# Adj.net
KiCad netlist of a schematic drawn in EAGLE
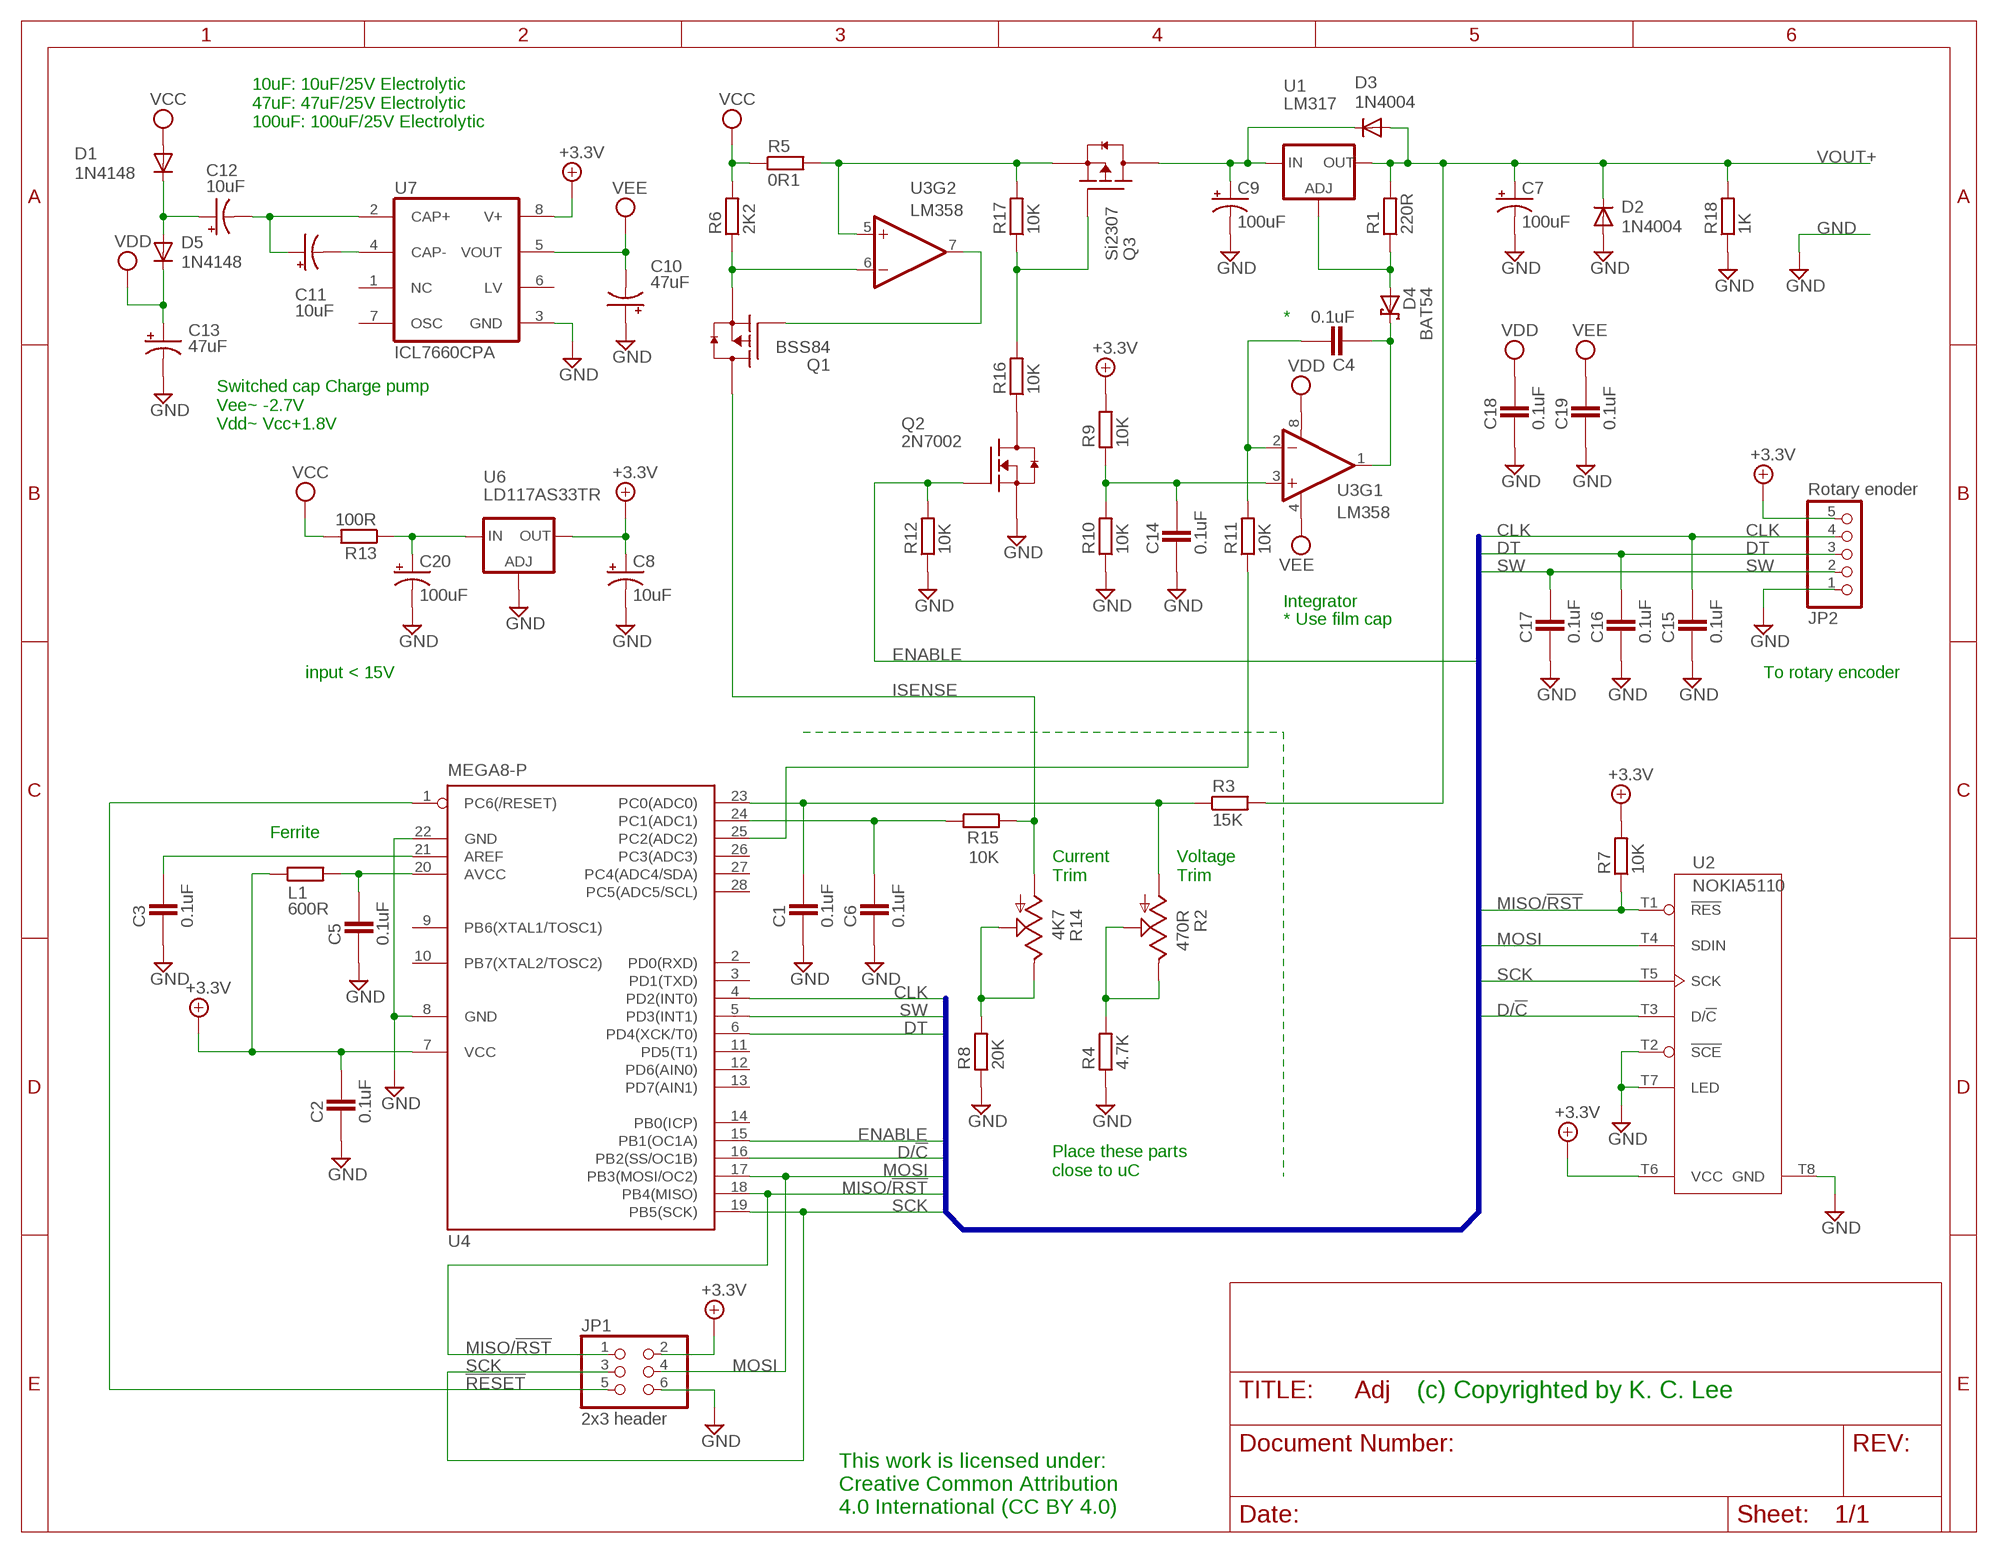
[diagram p0: schematic, sheet 1]

(export (version "E")
  (design (tool "Eeschema 10.0.6"))
  (components
    (comp (ref "C1")
      (value "0.1uF")
      (footprint "eagle-import:CAPC2012X145AN")
      (libsource (lib "eagle-import") (part "CAPACITOR_0805"))
    )
    (comp (ref "C2")
      (value "0.1uF")
      (footprint "eagle-import:CAPC2012X145AN")
      (libsource (lib "eagle-import") (part "CAPACITOR_0805"))
    )
    (comp (ref "C3")
      (value "0.1uF")
      (footprint "eagle-import:CAPC2012X145AN")
      (libsource (lib "eagle-import") (part "CAPACITOR_0805"))
    )
    (comp (ref "C4")
      (value "0.1uF")
      (footprint "eagle-import:CAPC2012X145AN")
      (libsource (lib "eagle-import") (part "CAPACITOR_0805"))
    )
    (comp (ref "C5")
      (value "0.1uF")
      (footprint "eagle-import:CAPC2012X145AN")
      (libsource (lib "eagle-import") (part "CAPACITOR_0805"))
    )
    (comp (ref "C6")
      (value "0.1uF")
      (footprint "eagle-import:CAPC2012X145AN")
      (libsource (lib "eagle-import") (part "CAPACITOR_0805"))
    )
    (comp (ref "C7")
      (value "100uF")
      (footprint "eagle-import:E2,5-6E")
      (fields (field (name "PARTNO") "100uF/25V"))
      (libsource (lib "eagle-import") (part "CAP_POL"))
    )
    (comp (ref "C8")
      (value "10uF")
      (footprint "eagle-import:E2,5-6E")
      (fields (field (name "PARTNO") "10uF/25V"))
      (libsource (lib "eagle-import") (part "CAP_POL"))
    )
    (comp (ref "C9")
      (value "100uF")
      (footprint "eagle-import:E2,5-6E")
      (fields (field (name "PARTNO") "100uF/25V"))
      (libsource (lib "eagle-import") (part "CAP_POL"))
    )
    (comp (ref "C10")
      (value "47uF")
      (footprint "eagle-import:E2,5-6E")
      (fields (field (name "PARTNO") "47uF/25V"))
      (libsource (lib "eagle-import") (part "CAP_POL"))
    )
    (comp (ref "C11")
      (value "10uF")
      (footprint "eagle-import:E2,5-6E")
      (fields (field (name "PARTNO") "10uF/25V"))
      (libsource (lib "eagle-import") (part "CAP_POL"))
    )
    (comp (ref "C12")
      (value "10uF")
      (footprint "eagle-import:E2,5-6E")
      (fields (field (name "PARTNO") "10uF/25V"))
      (libsource (lib "eagle-import") (part "CAP_POL"))
    )
    (comp (ref "C13")
      (value "47uF")
      (footprint "eagle-import:E2,5-6E")
      (fields (field (name "PARTNO") "47uF/25V"))
      (libsource (lib "eagle-import") (part "CAP_POL"))
    )
    (comp (ref "C14")
      (value "0.1uF")
      (footprint "eagle-import:CAPC2012X145AN")
      (libsource (lib "eagle-import") (part "CAPACITOR_0805"))
    )
    (comp (ref "C15")
      (value "0.1uF")
      (footprint "eagle-import:CAPC2012X145AN")
      (libsource (lib "eagle-import") (part "CAPACITOR_0805"))
    )
    (comp (ref "C16")
      (value "0.1uF")
      (footprint "eagle-import:CAPC2012X145AN")
      (libsource (lib "eagle-import") (part "CAPACITOR_0805"))
    )
    (comp (ref "C17")
      (value "0.1uF")
      (footprint "eagle-import:CAPC2012X145AN")
      (libsource (lib "eagle-import") (part "CAPACITOR_0805"))
    )
    (comp (ref "C18")
      (value "0.1uF")
      (footprint "eagle-import:CAPC2012X145AN")
      (libsource (lib "eagle-import") (part "CAPACITOR_0805"))
    )
    (comp (ref "C19")
      (value "0.1uF")
      (footprint "eagle-import:CAPC2012X145AN")
      (libsource (lib "eagle-import") (part "CAPACITOR_0805"))
    )
    (comp (ref "C20")
      (value "100uF")
      (footprint "eagle-import:E2,5-6E")
      (fields (field (name "PARTNO") "100uF/25V"))
      (libsource (lib "eagle-import") (part "CAP_POL"))
    )
    (comp (ref "D1")
      (value "1N4148")
      (footprint "eagle-import:DO35-7")
      (libsource (lib "eagle-import") (part "1N4148DO35-7"))
    )
    (comp (ref "D2")
      (value "1N4004")
      (footprint "eagle-import:DO41-10")
      (libsource (lib "eagle-import") (part "1N4004"))
    )
    (comp (ref "D3")
      (value "1N4004")
      (footprint "eagle-import:DO41-10")
      (libsource (lib "eagle-import") (part "1N4004"))
    )
    (comp (ref "D4")
      (value "BAT54")
      (footprint "eagle-import:SOT95P280X135-3N")
      (libsource (lib "eagle-import") (part "SCHOTTKY_SOT-23"))
    )
    (comp (ref "D5")
      (value "1N4148")
      (footprint "eagle-import:DO35-7")
      (libsource (lib "eagle-import") (part "1N4148DO35-7"))
    )
    (comp (ref "JP1")
      (value "2x3 header")
      (footprint "eagle-import:2X03")
      (libsource (lib "eagle-import") (part "PINHD-2X3_2.54"))
    )
    (comp (ref "JP2")
      (value "Rotary enoder")
      (footprint "eagle-import:1X05")
      (libsource (lib "eagle-import") (part "PINHD-1X5_2.54"))
    )
    (comp (ref "L1")
      (value "600R")
      (footprint "eagle-import:RESC1608X55N")
      (fields (field (name "PARTNO") "Ferrite 600R@100MHz"))
      (libsource (lib "eagle-import") (part "RESISTOR_0603"))
    )
    (comp (ref "Q1")
      (value "BSS84")
      (footprint "eagle-import:SOT95P280X135-3N")
      (libsource (lib "eagle-import") (part "MOSFET-PCH_SOT-23"))
    )
    (comp (ref "Q2")
      (value "2N7002")
      (footprint "eagle-import:SOT95P280X135-3N")
      (libsource (lib "eagle-import") (part "MOSFET-NCH_SOT-23"))
    )
    (comp (ref "Q3")
      (value "Si2307")
      (footprint "eagle-import:SOT95P280X135-3N")
      (libsource (lib "eagle-import") (part "MOSFET-PCH_SOT-23"))
    )
    (comp (ref "R1")
      (value "220R")
      (footprint "eagle-import:RESC1608X55N")
      (libsource (lib "eagle-import") (part "RESISTOR_0603"))
    )
    (comp (ref "R2")
      (value "470R")
      (footprint "eagle-import:B25U")
      (libsource (lib "eagle-import") (part "TRIM_US-B25U"))
    )
    (comp (ref "R3")
      (value "15K")
      (footprint "eagle-import:RESC1608X55N")
      (libsource (lib "eagle-import") (part "RESISTOR_0603"))
    )
    (comp (ref "R4")
      (value "4.7K")
      (footprint "eagle-import:RESC1608X55N")
      (libsource (lib "eagle-import") (part "RESISTOR_0603"))
    )
    (comp (ref "R5")
      (value "0R1")
      (footprint "eagle-import:RESC1608X55N")
      (fields (field (name "PARTNO") "0R1 1W"))
      (libsource (lib "eagle-import") (part "RESISTOR_0603"))
    )
    (comp (ref "R6")
      (value "2K2")
      (footprint "eagle-import:RESC1608X55N")
      (libsource (lib "eagle-import") (part "RESISTOR_0603"))
    )
    (comp (ref "R7")
      (value "10K")
      (footprint "eagle-import:RESC1608X55N")
      (libsource (lib "eagle-import") (part "RESISTOR_0603"))
    )
    (comp (ref "R8")
      (value "20K")
      (footprint "eagle-import:RESC1608X55N")
      (libsource (lib "eagle-import") (part "RESISTOR_0603"))
    )
    (comp (ref "R9")
      (value "10K")
      (footprint "eagle-import:RESC1608X55N")
      (libsource (lib "eagle-import") (part "RESISTOR_0603"))
    )
    (comp (ref "R10")
      (value "10K")
      (footprint "eagle-import:RESC1608X55N")
      (libsource (lib "eagle-import") (part "RESISTOR_0603"))
    )
    (comp (ref "R11")
      (value "10K")
      (footprint "eagle-import:RESC1608X55N")
      (libsource (lib "eagle-import") (part "RESISTOR_0603"))
    )
    (comp (ref "R12")
      (value "10K")
      (footprint "eagle-import:RESC1608X55N")
      (libsource (lib "eagle-import") (part "RESISTOR_0603"))
    )
    (comp (ref "R13")
      (value "100R")
      (footprint "eagle-import:RESC1608X55N")
      (libsource (lib "eagle-import") (part "RESISTOR_0603"))
    )
    (comp (ref "R14")
      (value "4K7")
      (footprint "eagle-import:B25U")
      (libsource (lib "eagle-import") (part "TRIM_US-B25U"))
    )
    (comp (ref "R15")
      (value "10K")
      (footprint "eagle-import:RESC1608X55N")
      (libsource (lib "eagle-import") (part "RESISTOR_0603"))
    )
    (comp (ref "R16")
      (value "10K")
      (footprint "eagle-import:RESC1608X55N")
      (libsource (lib "eagle-import") (part "RESISTOR_0603"))
    )
    (comp (ref "R17")
      (value "10K")
      (footprint "eagle-import:RESC1608X55N")
      (libsource (lib "eagle-import") (part "RESISTOR_0603"))
    )
    (comp (ref "R18")
      (value "1K")
      (footprint "eagle-import:RESC1608X55N")
      (libsource (lib "eagle-import") (part "RESISTOR_0603"))
    )
    (comp (ref "U1")
      (value "LM317")
      (footprint "eagle-import:TO220-ADJ")
      (libsource (lib "eagle-import") (part "V_REG_317SINK"))
    )
    (comp (ref "U2")
      (value "NOKIA5110")
      (footprint "eagle-import:NOKIA5110-ALT-TOP")
      (fields (field (name "PARTNO") "Nokia 5110 LCD"))
      (libsource (lib "eagle-import") (part "NOKIA5110ALT-TOP"))
    )
    (comp (ref "U3")
      (value "LM358")
      (footprint "eagle-import:DIP08")
      (fields (field (name "PARTNO") "*"))
      (libsource (lib "eagle-import") (part "LM358"))
    )
    (comp (ref "U4")
      (value "MEGA8-P")
      (footprint "eagle-import:DIL28-3")
      (fields (field (name "PARTNO") "ATMerga8A"))
      (libsource (lib "eagle-import") (part "MEGA8-P"))
    )
    (comp (ref "U6")
      (value "LD117AS33TR")
      (footprint "eagle-import:SOT223")
      (libsource (lib "eagle-import") (part "LD117A?S33TR"))
    )
    (comp (ref "U7")
      (value "ICL7660CPA")
      (footprint "eagle-import:DIL08")
      (fields (field (name "MF") "INTERSIL"))
      (libsource (lib "eagle-import") (part "ICL7660CPA"))
    )
  )
  (nets
    (net (code "1") (name "+3.3V") (class "Default")
      (node (ref "C2") (pin "2") (pinfunction "2_2") (pintype "passive"))
      (node (ref "C8") (pin "+") (pinfunction "+_+") (pintype "passive"))
      (node (ref "JP1") (pin "2") (pinfunction "2_2") (pintype "passive"))
      (node (ref "JP2") (pin "5") (pinfunction "5_5") (pintype "passive"))
      (node (ref "L1") (pin "1") (pinfunction "1_1") (pintype "passive"))
      (node (ref "R7") (pin "2") (pinfunction "2_2") (pintype "passive"))
      (node (ref "R9") (pin "2") (pinfunction "2_2") (pintype "passive"))
      (node (ref "U2") (pin "T6") (pinfunction "VCC_T6") (pintype "input"))
      (node (ref "U4") (pin "7") (pinfunction "VCC_7") (pintype "power_in"))
      (node (ref "U6") (pin "2") (pinfunction "OUT_2") (pintype "passive"))
      (node (ref "U6") (pin "4") (pinfunction "OUT_4") (pintype "passive"))
      (node (ref "U7") (pin "8") (pinfunction "V+_8") (pintype "power_in"))
    )
    (net (code "2") (name "/CLK") (class "Default")
      (node (ref "C15") (pin "2") (pinfunction "2_2") (pintype "passive"))
      (node (ref "JP2") (pin "4") (pinfunction "4_4") (pintype "passive"))
      (node (ref "U4") (pin "4") (pinfunction "PD2(INT0)_4") (pintype "bidirectional"))
    )
    (net (code "3") (name "/DT") (class "Default")
      (node (ref "C16") (pin "2") (pinfunction "2_2") (pintype "passive"))
      (node (ref "JP2") (pin "3") (pinfunction "3_3") (pintype "passive"))
      (node (ref "U4") (pin "6") (pinfunction "PD4(XCK/T0)_6") (pintype "bidirectional"))
    )
    (net (code "4") (name "/D{slash}~{C}") (class "Default")
      (node (ref "U2") (pin "T3") (pinfunction "D/~{C}_T3") (pintype "input"))
      (node (ref "U4") (pin "16") (pinfunction "PB2(SS/OC1B)_16") (pintype "bidirectional"))
    )
    (net (code "5") (name "/ENABLE") (class "Default")
      (node (ref "Q2") (pin "1") (pinfunction "G_1") (pintype "passive"))
      (node (ref "R12") (pin "2") (pinfunction "2_2") (pintype "passive"))
      (node (ref "U4") (pin "15") (pinfunction "PB1(OC1A)_15") (pintype "bidirectional"))
    )
    (net (code "6") (name "/ISENSE") (class "Default")
      (node (ref "Q1") (pin "3") (pinfunction "D_3") (pintype "passive"))
      (node (ref "R14") (pin "A") (pinfunction "A_A") (pintype "passive"))
      (node (ref "R15") (pin "1") (pinfunction "1_1") (pintype "passive"))
    )
    (net (code "7") (name "/MISO{slash}~{RST}") (class "Default")
      (node (ref "JP1") (pin "1") (pinfunction "1_1") (pintype "passive"))
      (node (ref "R7") (pin "1") (pinfunction "1_1") (pintype "passive"))
      (node (ref "U2") (pin "T1") (pinfunction "~{RES}_T1") (pintype "input"))
      (node (ref "U4") (pin "18") (pinfunction "PB4(MISO)_18") (pintype "bidirectional"))
    )
    (net (code "8") (name "/MOSI") (class "Default")
      (node (ref "JP1") (pin "4") (pinfunction "4_4") (pintype "passive"))
      (node (ref "U2") (pin "T4") (pinfunction "SDIN_T4") (pintype "input"))
      (node (ref "U4") (pin "17") (pinfunction "PB3(MOSI/OC2)_17") (pintype "bidirectional"))
    )
    (net (code "9") (name "/SCK") (class "Default")
      (node (ref "JP1") (pin "3") (pinfunction "3_3") (pintype "passive"))
      (node (ref "U2") (pin "T5") (pinfunction "SCK_T5") (pintype "input"))
      (node (ref "U4") (pin "19") (pinfunction "PB5(SCK)_19") (pintype "bidirectional"))
    )
    (net (code "10") (name "/SW") (class "Default")
      (node (ref "C17") (pin "2") (pinfunction "2_2") (pintype "passive"))
      (node (ref "JP2") (pin "2") (pinfunction "2_2") (pintype "passive"))
      (node (ref "U4") (pin "5") (pinfunction "PD3(INT1)_5") (pintype "bidirectional"))
    )
    (net (code "11") (name "/VOUT+") (class "Default")
      (node (ref "C7") (pin "+") (pinfunction "+_+") (pintype "passive"))
      (node (ref "D2") (pin "C") (pinfunction "C_C") (pintype "passive"))
      (node (ref "D3") (pin "A") (pinfunction "A_A") (pintype "passive"))
      (node (ref "R1") (pin "2") (pinfunction "2_2") (pintype "passive"))
      (node (ref "R18") (pin "2") (pinfunction "2_2") (pintype "passive"))
      (node (ref "R3") (pin "2") (pinfunction "2_2") (pintype "passive"))
      (node (ref "U1") (pin "OUT") (pinfunction "OUT_OUT") (pintype "output"))
    )
    (net (code "12") (name "/~{RESET}") (class "Default")
      (node (ref "JP1") (pin "5") (pinfunction "5_5") (pintype "passive"))
      (node (ref "U4") (pin "1") (pinfunction "PC6(/RESET)_1") (pintype "bidirectional"))
    )
    (net (code "13") (name "GND") (class "Default")
      (node (ref "C1") (pin "1") (pinfunction "1_1") (pintype "passive"))
      (node (ref "C10") (pin "+") (pinfunction "+_+") (pintype "passive"))
      (node (ref "C13") (pin "-") (pinfunction "-_-") (pintype "passive"))
      (node (ref "C14") (pin "1") (pinfunction "1_1") (pintype "passive"))
      (node (ref "C15") (pin "1") (pinfunction "1_1") (pintype "passive"))
      (node (ref "C16") (pin "1") (pinfunction "1_1") (pintype "passive"))
      (node (ref "C17") (pin "1") (pinfunction "1_1") (pintype "passive"))
      (node (ref "C18") (pin "1") (pinfunction "1_1") (pintype "passive"))
      (node (ref "C19") (pin "1") (pinfunction "1_1") (pintype "passive"))
      (node (ref "C2") (pin "1") (pinfunction "1_1") (pintype "passive"))
      (node (ref "C20") (pin "-") (pinfunction "-_-") (pintype "passive"))
      (node (ref "C3") (pin "1") (pinfunction "1_1") (pintype "passive"))
      (node (ref "C5") (pin "1") (pinfunction "1_1") (pintype "passive"))
      (node (ref "C6") (pin "1") (pinfunction "1_1") (pintype "passive"))
      (node (ref "C7") (pin "-") (pinfunction "-_-") (pintype "passive"))
      (node (ref "C8") (pin "-") (pinfunction "-_-") (pintype "passive"))
      (node (ref "C9") (pin "-") (pinfunction "-_-") (pintype "passive"))
      (node (ref "D2") (pin "A") (pinfunction "A_A") (pintype "passive"))
      (node (ref "JP1") (pin "6") (pinfunction "6_6") (pintype "passive"))
      (node (ref "JP2") (pin "1") (pinfunction "1_1") (pintype "passive"))
      (node (ref "Q2") (pin "2") (pinfunction "S_2") (pintype "passive"))
      (node (ref "R10") (pin "1") (pinfunction "1_1") (pintype "passive"))
      (node (ref "R12") (pin "1") (pinfunction "1_1") (pintype "passive"))
      (node (ref "R18") (pin "1") (pinfunction "1_1") (pintype "passive"))
      (node (ref "R4") (pin "1") (pinfunction "1_1") (pintype "passive"))
      (node (ref "R8") (pin "1") (pinfunction "1_1") (pintype "passive"))
      (node (ref "U2") (pin "T2") (pinfunction "~{SCE}_T2") (pintype "input"))
      (node (ref "U2") (pin "T7") (pinfunction "LED_T7") (pintype "input"))
      (node (ref "U2") (pin "T8") (pinfunction "GND_T8") (pintype "input"))
      (node (ref "U4") (pin "22") (pinfunction "GND_22") (pintype "power_in"))
      (node (ref "U4") (pin "8") (pinfunction "GND_8") (pintype "power_in"))
      (node (ref "U6") (pin "1") (pinfunction "ADJ_1") (pintype "input"))
      (node (ref "U7") (pin "3") (pinfunction "GND_3") (pintype "power_in"))
    )
    (net (code "14") (name "Net-(C12-Pad+)") (class "Default")
      (node (ref "C12") (pin "+") (pinfunction "+_+") (pintype "passive"))
      (node (ref "D1") (pin "C") (pinfunction "C_C") (pintype "passive"))
      (node (ref "D5") (pin "A") (pinfunction "A_A") (pintype "passive"))
    )
    (net (code "15") (name "Net-(D4-A)") (class "Default")
      (node (ref "D4") (pin "1") (pinfunction "A_1") (pintype "passive"))
      (node (ref "R1") (pin "1") (pinfunction "1_1") (pintype "passive"))
      (node (ref "U1") (pin "ADJ") (pinfunction "ADJ_ADJ") (pintype "input"))
    )
    (net (code "16") (name "Net-(D4-K)") (class "Default")
      (node (ref "C4") (pin "1") (pinfunction "1_1") (pintype "passive"))
      (node (ref "D4") (pin "3") (pinfunction "K_3") (pintype "passive"))
      (node (ref "U3") (pin "1") (pinfunction "OUT_1") (pintype "output"))
    )
    (net (code "17") (name "Net-(Q1-G)") (class "Default")
      (node (ref "Q1") (pin "1") (pinfunction "G_1") (pintype "passive"))
      (node (ref "U3") (pin "7") (pinfunction "OUT_7") (pintype "output"))
    )
    (net (code "18") (name "Net-(Q1-S)") (class "Default")
      (node (ref "Q1") (pin "2") (pinfunction "S_2") (pintype "passive"))
      (node (ref "R6") (pin "1") (pinfunction "1_1") (pintype "passive"))
      (node (ref "U3") (pin "6") (pinfunction "-IN_6") (pintype "input"))
    )
    (net (code "19") (name "Net-(Q2-D)") (class "Default")
      (node (ref "Q2") (pin "3") (pinfunction "D_3") (pintype "passive"))
      (node (ref "R16") (pin "1") (pinfunction "1_1") (pintype "passive"))
    )
    (net (code "20") (name "Net-(Q3-D)") (class "Default")
      (node (ref "C9") (pin "+") (pinfunction "+_+") (pintype "passive"))
      (node (ref "D3") (pin "C") (pinfunction "C_C") (pintype "passive"))
      (node (ref "Q3") (pin "3") (pinfunction "D_3") (pintype "passive"))
      (node (ref "U1") (pin "IN") (pinfunction "IN_IN") (pintype "input"))
    )
    (net (code "21") (name "Net-(Q3-G)") (class "Default")
      (node (ref "Q3") (pin "1") (pinfunction "G_1") (pintype "passive"))
      (node (ref "R16") (pin "2") (pinfunction "2_2") (pintype "passive"))
      (node (ref "R17") (pin "1") (pinfunction "1_1") (pintype "passive"))
    )
    (net (code "22") (name "Net-(Q3-S)") (class "Default")
      (node (ref "Q3") (pin "2") (pinfunction "S_2") (pintype "passive"))
      (node (ref "R17") (pin "2") (pinfunction "2_2") (pintype "passive"))
      (node (ref "R5") (pin "2") (pinfunction "2_2") (pintype "passive"))
      (node (ref "U3") (pin "5") (pinfunction "+IN_5") (pintype "input"))
    )
    (net (code "23") (name "Net-(R2-PadE)") (class "Default")
      (node (ref "R2") (pin "E") (pinfunction "E_E") (pintype "passive"))
      (node (ref "R2") (pin "S") (pinfunction "S_S") (pintype "passive"))
      (node (ref "R4") (pin "2") (pinfunction "2_2") (pintype "passive"))
    )
    (net (code "24") (name "Net-(R14-PadE)") (class "Default")
      (node (ref "R14") (pin "E") (pinfunction "E_E") (pintype "passive"))
      (node (ref "R14") (pin "S") (pinfunction "S_S") (pintype "passive"))
      (node (ref "R8") (pin "2") (pinfunction "2_2") (pintype "passive"))
    )
    (net (code "25") (name "Net-(U3A-+IN)") (class "Default")
      (node (ref "C14") (pin "2") (pinfunction "2_2") (pintype "passive"))
      (node (ref "R10") (pin "2") (pinfunction "2_2") (pintype "passive"))
      (node (ref "R9") (pin "1") (pinfunction "1_1") (pintype "passive"))
      (node (ref "U3") (pin "3") (pinfunction "+IN_3") (pintype "input"))
    )
    (net (code "26") (name "Net-(U3A--IN)") (class "Default")
      (node (ref "C4") (pin "2") (pinfunction "2_2") (pintype "passive"))
      (node (ref "R11") (pin "2") (pinfunction "2_2") (pintype "passive"))
      (node (ref "U3") (pin "2") (pinfunction "-IN_2") (pintype "input"))
    )
    (net (code "27") (name "Net-(U4-AREF)") (class "Default")
      (node (ref "C3") (pin "2") (pinfunction "2_2") (pintype "passive"))
      (node (ref "U4") (pin "21") (pinfunction "AREF_21") (pintype "passive"))
    )
    (net (code "28") (name "Net-(U4-AVCC)") (class "Default")
      (node (ref "C5") (pin "2") (pinfunction "2_2") (pintype "passive"))
      (node (ref "L1") (pin "2") (pinfunction "2_2") (pintype "passive"))
      (node (ref "U4") (pin "20") (pinfunction "AVCC_20") (pintype "power_in"))
    )
    (net (code "29") (name "Net-(U4-PC0(ADC0))") (class "Default")
      (node (ref "C1") (pin "2") (pinfunction "2_2") (pintype "passive"))
      (node (ref "R2") (pin "A") (pinfunction "A_A") (pintype "passive"))
      (node (ref "R3") (pin "1") (pinfunction "1_1") (pintype "passive"))
      (node (ref "U4") (pin "23") (pinfunction "PC0(ADC0)_23") (pintype "bidirectional"))
    )
    (net (code "30") (name "Net-(U4-PC1(ADC1))") (class "Default")
      (node (ref "C6") (pin "2") (pinfunction "2_2") (pintype "passive"))
      (node (ref "R15") (pin "2") (pinfunction "2_2") (pintype "passive"))
      (node (ref "U4") (pin "24") (pinfunction "PC1(ADC1)_24") (pintype "bidirectional"))
    )
    (net (code "31") (name "Net-(U4-PC2(ADC2))") (class "Default")
      (node (ref "R11") (pin "1") (pinfunction "1_1") (pintype "passive"))
      (node (ref "U4") (pin "25") (pinfunction "PC2(ADC2)_25") (pintype "bidirectional"))
    )
    (net (code "32") (name "Net-(U6-IN)") (class "Default")
      (node (ref "C20") (pin "+") (pinfunction "+_+") (pintype "passive"))
      (node (ref "R13") (pin "1") (pinfunction "1_1") (pintype "passive"))
      (node (ref "U6") (pin "3") (pinfunction "IN_3") (pintype "input"))
    )
    (net (code "33") (name "Net-(U7-CAP+)") (class "Default")
      (node (ref "C11") (pin "+") (pinfunction "+_+") (pintype "passive"))
      (node (ref "C12") (pin "-") (pinfunction "-_-") (pintype "passive"))
      (node (ref "U7") (pin "2") (pinfunction "CAP+_2") (pintype "passive"))
    )
    (net (code "34") (name "Net-(U7-CAP-)") (class "Default")
      (node (ref "C11") (pin "-") (pinfunction "-_-") (pintype "passive"))
      (node (ref "U7") (pin "4") (pinfunction "CAP-_4") (pintype "passive"))
    )
    (net (code "35") (name "VCC") (class "Default")
      (node (ref "D1") (pin "A") (pinfunction "A_A") (pintype "passive"))
      (node (ref "R13") (pin "2") (pinfunction "2_2") (pintype "passive"))
      (node (ref "R5") (pin "1") (pinfunction "1_1") (pintype "passive"))
      (node (ref "R6") (pin "2") (pinfunction "2_2") (pintype "passive"))
    )
    (net (code "36") (name "VDD") (class "Default")
      (node (ref "C13") (pin "+") (pinfunction "+_+") (pintype "passive"))
      (node (ref "C18") (pin "2") (pinfunction "2_2") (pintype "passive"))
      (node (ref "D5") (pin "C") (pinfunction "C_C") (pintype "passive"))
      (node (ref "U3") (pin "8") (pinfunction "V+_8") (pintype "power_in"))
    )
    (net (code "37") (name "VEE") (class "Default")
      (node (ref "C10") (pin "-") (pinfunction "-_-") (pintype "passive"))
      (node (ref "C19") (pin "2") (pinfunction "2_2") (pintype "passive"))
      (node (ref "U3") (pin "4") (pinfunction "V-_4") (pintype "power_in"))
      (node (ref "U7") (pin "5") (pinfunction "VOUT_5") (pintype "output"))
    )
    (net (code "38") (name "unconnected-(U4-PB0(ICP)-Pad14)") (class "Default")
      (node (ref "U4") (pin "14") (pinfunction "PB0(ICP)_14") (pintype "bidirectional"))
    )
    (net (code "39") (name "unconnected-(U4-PB6(XTAL1{slash}TOSC1)-Pad9)") (class "Default")
      (node (ref "U4") (pin "9") (pinfunction "PB6(XTAL1/TOSC1)_9") (pintype "bidirectional"))
    )
    (net (code "40") (name "unconnected-(U4-PB7(XTAL2{slash}TOSC2)-Pad10)") (class "Default")
      (node (ref "U4") (pin "10") (pinfunction "PB7(XTAL2/TOSC2)_10") (pintype "bidirectional"))
    )
    (net (code "41") (name "unconnected-(U4-PC3(ADC3)-Pad26)") (class "Default")
      (node (ref "U4") (pin "26") (pinfunction "PC3(ADC3)_26") (pintype "bidirectional"))
    )
    (net (code "42") (name "unconnected-(U4-PC4(ADC4{slash}SDA)-Pad27)") (class "Default")
      (node (ref "U4") (pin "27") (pinfunction "PC4(ADC4/SDA)_27") (pintype "bidirectional"))
    )
    (net (code "43") (name "unconnected-(U4-PC5(ADC5{slash}SCL)-Pad28)") (class "Default")
      (node (ref "U4") (pin "28") (pinfunction "PC5(ADC5/SCL)_28") (pintype "bidirectional"))
    )
    (net (code "44") (name "unconnected-(U4-PD0(RXD)-Pad2)") (class "Default")
      (node (ref "U4") (pin "2") (pinfunction "PD0(RXD)_2") (pintype "bidirectional"))
    )
    (net (code "45") (name "unconnected-(U4-PD1(TXD)-Pad3)") (class "Default")
      (node (ref "U4") (pin "3") (pinfunction "PD1(TXD)_3") (pintype "bidirectional"))
    )
    (net (code "46") (name "unconnected-(U4-PD5(T1)-Pad11)") (class "Default")
      (node (ref "U4") (pin "11") (pinfunction "PD5(T1)_11") (pintype "bidirectional"))
    )
    (net (code "47") (name "unconnected-(U4-PD6(AIN0)-Pad12)") (class "Default")
      (node (ref "U4") (pin "12") (pinfunction "PD6(AIN0)_12") (pintype "bidirectional"))
    )
    (net (code "48") (name "unconnected-(U4-PD7(AIN1)-Pad13)") (class "Default")
      (node (ref "U4") (pin "13") (pinfunction "PD7(AIN1)_13") (pintype "bidirectional"))
    )
    (net (code "49") (name "unconnected-(U7-LV-Pad6)") (class "Default")
      (node (ref "U7") (pin "6") (pinfunction "LV_6") (pintype "passive"))
    )
    (net (code "50") (name "unconnected-(U7-NC-Pad1)") (class "Default")
      (node (ref "U7") (pin "1") (pinfunction "NC_1") (pintype "no_connect"))
    )
    (net (code "51") (name "unconnected-(U7-OSC-Pad7)") (class "Default")
      (node (ref "U7") (pin "7") (pinfunction "OSC_7") (pintype "output"))
    )
  )
)
